# Juggling_Egg_V01.net
KiCad netlist of a schematic drawn in EAGLE
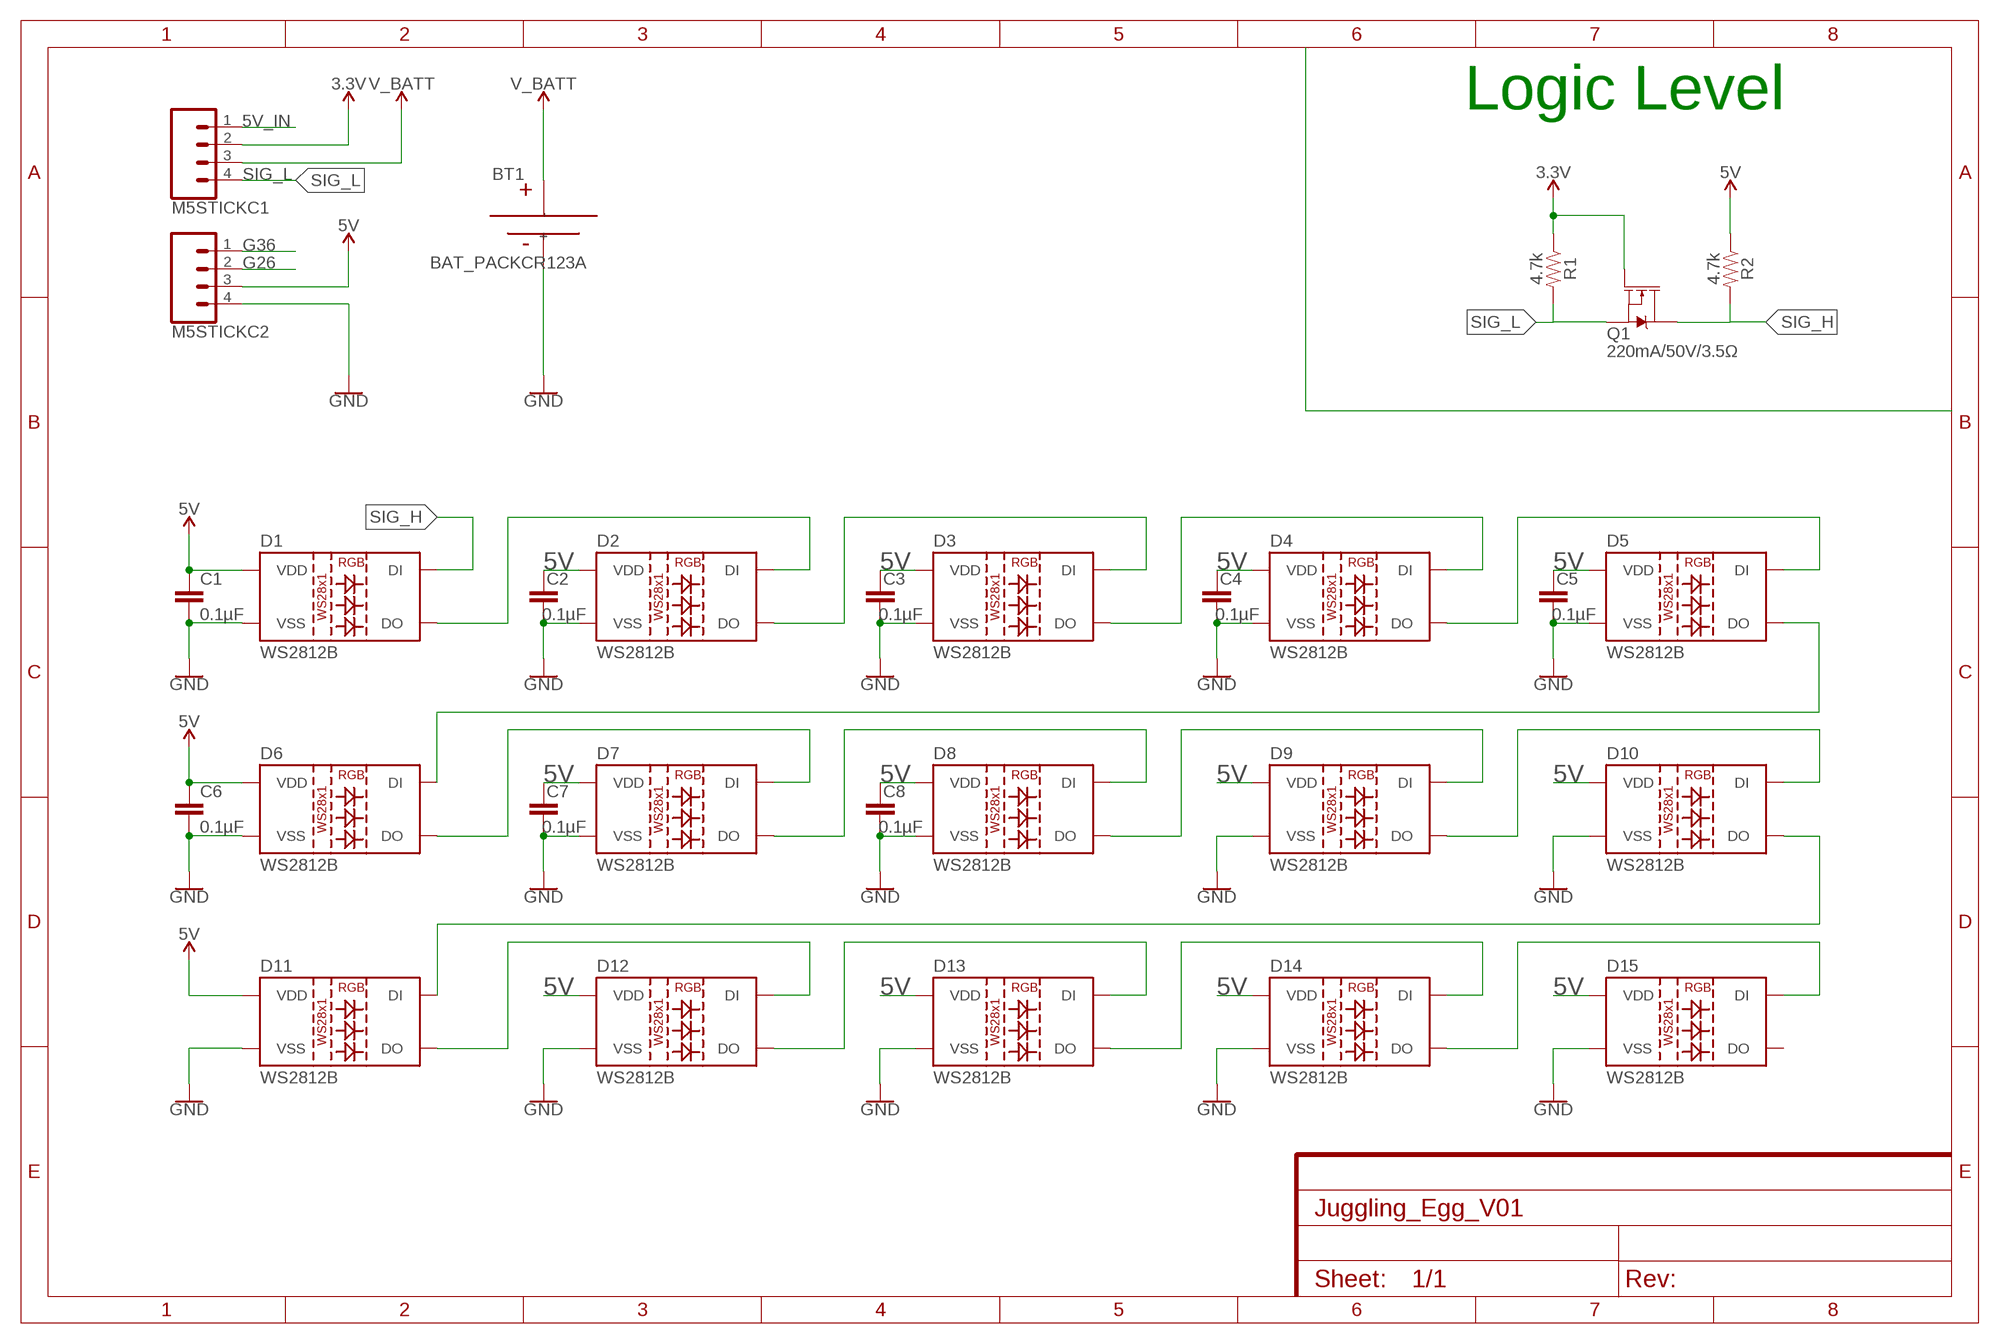
[diagram p0: schematic, sheet 1]

(export (version "E")
  (design (tool "Eeschema 10.0.6"))
  (components
    (comp (ref "BT1")
      (value "BAT_PACKCR123A")
      (footprint "eagle-import:BH123A")
      (fields (field (name "MANUFACTURER") "MPD") (field (name "MPN") "BH123A"))
      (libsource (lib "eagle-import") (part "BAT_PACKCR123A"))
    )
    (comp (ref "C1")
      (value "0.1µF")
      (footprint "eagle-import:0805")
      (libsource (lib "eagle-import") (part "0.33UF/330NF-0805-50V-10%"))
    )
    (comp (ref "C2")
      (value "0.1µF")
      (footprint "eagle-import:0805")
      (libsource (lib "eagle-import") (part "0.33UF/330NF-0805-50V-10%"))
    )
    (comp (ref "C3")
      (value "0.1µF")
      (footprint "eagle-import:0805")
      (libsource (lib "eagle-import") (part "0.33UF/330NF-0805-50V-10%"))
    )
    (comp (ref "C4")
      (value "0.1µF")
      (footprint "eagle-import:0805")
      (libsource (lib "eagle-import") (part "0.33UF/330NF-0805-50V-10%"))
    )
    (comp (ref "C5")
      (value "0.1µF")
      (footprint "eagle-import:0805")
      (libsource (lib "eagle-import") (part "0.33UF/330NF-0805-50V-10%"))
    )
    (comp (ref "C6")
      (value "0.1µF")
      (footprint "eagle-import:0805")
      (libsource (lib "eagle-import") (part "0.33UF/330NF-0805-50V-10%"))
    )
    (comp (ref "C7")
      (value "0.1µF")
      (footprint "eagle-import:0805")
      (libsource (lib "eagle-import") (part "0.33UF/330NF-0805-50V-10%"))
    )
    (comp (ref "C8")
      (value "0.1µF")
      (footprint "eagle-import:0805")
      (libsource (lib "eagle-import") (part "0.33UF/330NF-0805-50V-10%"))
    )
    (comp (ref "D1")
      (value "WS2812B")
      (footprint "eagle-import:WS2812B")
      (libsource (lib "eagle-import") (part "WS2812B"))
    )
    (comp (ref "D2")
      (value "WS2812B")
      (footprint "eagle-import:WS2812B")
      (libsource (lib "eagle-import") (part "WS2812B"))
    )
    (comp (ref "D3")
      (value "WS2812B")
      (footprint "eagle-import:WS2812B")
      (libsource (lib "eagle-import") (part "WS2812B"))
    )
    (comp (ref "D4")
      (value "WS2812B")
      (footprint "eagle-import:WS2812B")
      (libsource (lib "eagle-import") (part "WS2812B"))
    )
    (comp (ref "D5")
      (value "WS2812B")
      (footprint "eagle-import:WS2812B")
      (libsource (lib "eagle-import") (part "WS2812B"))
    )
    (comp (ref "D6")
      (value "WS2812B")
      (footprint "eagle-import:WS2812B")
      (libsource (lib "eagle-import") (part "WS2812B"))
    )
    (comp (ref "D7")
      (value "WS2812B")
      (footprint "eagle-import:WS2812B")
      (libsource (lib "eagle-import") (part "WS2812B"))
    )
    (comp (ref "D8")
      (value "WS2812B")
      (footprint "eagle-import:WS2812B")
      (libsource (lib "eagle-import") (part "WS2812B"))
    )
    (comp (ref "D9")
      (value "WS2812B")
      (footprint "eagle-import:WS2812B")
      (libsource (lib "eagle-import") (part "WS2812B"))
    )
    (comp (ref "D10")
      (value "WS2812B")
      (footprint "eagle-import:WS2812B")
      (libsource (lib "eagle-import") (part "WS2812B"))
    )
    (comp (ref "D11")
      (value "WS2812B")
      (footprint "eagle-import:WS2812B")
      (libsource (lib "eagle-import") (part "WS2812B"))
    )
    (comp (ref "D12")
      (value "WS2812B")
      (footprint "eagle-import:WS2812B")
      (libsource (lib "eagle-import") (part "WS2812B"))
    )
    (comp (ref "D13")
      (value "WS2812B")
      (footprint "eagle-import:WS2812B")
      (libsource (lib "eagle-import") (part "WS2812B"))
    )
    (comp (ref "D14")
      (value "WS2812B")
      (footprint "eagle-import:WS2812B")
      (libsource (lib "eagle-import") (part "WS2812B"))
    )
    (comp (ref "D15")
      (value "WS2812B")
      (footprint "eagle-import:WS2812B")
      (libsource (lib "eagle-import") (part "WS2812B"))
    )
    (comp (ref "M5STICKC1")
      (value "CONN_04SMD")
      (footprint "eagle-import:1X04_SMD_RA_MALE")
      (libsource (lib "eagle-import") (part "CONN_04SMD"))
    )
    (comp (ref "M5STICKC2")
      (value "CONN_04SMD")
      (footprint "eagle-import:1X04_SMD_RA_MALE")
      (libsource (lib "eagle-import") (part "CONN_04SMD"))
    )
    (comp (ref "Q1")
      (value "220mA/50V/3.5Ω")
      (footprint "eagle-import:SOT23-3")
      (libsource (lib "eagle-import") (part "MOSFET-NCH-BSS138"))
    )
    (comp (ref "R1")
      (value "4.7k")
      (footprint "eagle-import:0805")
      (libsource (lib "eagle-import") (part "RESISTOR0805"))
    )
    (comp (ref "R2")
      (value "4.7k")
      (footprint "eagle-import:0805")
      (libsource (lib "eagle-import") (part "RESISTOR0805"))
    )
  )
  (nets
    (net (code "1") (name "/5V_IN") (class "Default")
      (node (ref "M5STICKC1") (pin "1") (pinfunction "1_1") (pintype "passive"))
    )
    (net (code "2") (name "/G26") (class "Default")
      (node (ref "M5STICKC2") (pin "2") (pinfunction "2_2") (pintype "passive"))
    )
    (net (code "3") (name "/G36") (class "Default")
      (node (ref "M5STICKC2") (pin "1") (pinfunction "1_1") (pintype "passive"))
    )
    (net (code "4") (name "3.3V") (class "Default")
      (node (ref "M5STICKC1") (pin "2") (pinfunction "2_2") (pintype "passive"))
      (node (ref "Q1") (pin "1") (pinfunction "G_1") (pintype "bidirectional"))
      (node (ref "R1") (pin "1") (pinfunction "1_1") (pintype "passive"))
    )
    (net (code "5") (name "5V") (class "Default")
      (node (ref "C1") (pin "1") (pinfunction "1_1") (pintype "passive"))
      (node (ref "C2") (pin "2") (pinfunction "2_2") (pintype "passive"))
      (node (ref "C3") (pin "2") (pinfunction "2_2") (pintype "passive"))
      (node (ref "C4") (pin "2") (pinfunction "2_2") (pintype "passive"))
      (node (ref "C5") (pin "2") (pinfunction "2_2") (pintype "passive"))
      (node (ref "C6") (pin "1") (pinfunction "1_1") (pintype "passive"))
      (node (ref "C7") (pin "2") (pinfunction "2_2") (pintype "passive"))
      (node (ref "C8") (pin "2") (pinfunction "2_2") (pintype "passive"))
      (node (ref "D1") (pin "1") (pinfunction "VDD_1") (pintype "bidirectional"))
      (node (ref "D10") (pin "1") (pinfunction "VDD_1") (pintype "bidirectional"))
      (node (ref "D11") (pin "1") (pinfunction "VDD_1") (pintype "bidirectional"))
      (node (ref "D12") (pin "1") (pinfunction "VDD_1") (pintype "bidirectional"))
      (node (ref "D13") (pin "1") (pinfunction "VDD_1") (pintype "bidirectional"))
      (node (ref "D14") (pin "1") (pinfunction "VDD_1") (pintype "bidirectional"))
      (node (ref "D15") (pin "1") (pinfunction "VDD_1") (pintype "bidirectional"))
      (node (ref "D2") (pin "1") (pinfunction "VDD_1") (pintype "bidirectional"))
      (node (ref "D3") (pin "1") (pinfunction "VDD_1") (pintype "bidirectional"))
      (node (ref "D4") (pin "1") (pinfunction "VDD_1") (pintype "bidirectional"))
      (node (ref "D5") (pin "1") (pinfunction "VDD_1") (pintype "bidirectional"))
      (node (ref "D6") (pin "1") (pinfunction "VDD_1") (pintype "bidirectional"))
      (node (ref "D7") (pin "1") (pinfunction "VDD_1") (pintype "bidirectional"))
      (node (ref "D8") (pin "1") (pinfunction "VDD_1") (pintype "bidirectional"))
      (node (ref "D9") (pin "1") (pinfunction "VDD_1") (pintype "bidirectional"))
      (node (ref "M5STICKC2") (pin "3") (pinfunction "3_3") (pintype "passive"))
      (node (ref "R2") (pin "1") (pinfunction "1_1") (pintype "passive"))
    )
    (net (code "6") (name "GND") (class "Default")
      (node (ref "BT1") (pin "-") (pinfunction "-_-") (pintype "bidirectional"))
      (node (ref "C1") (pin "2") (pinfunction "2_2") (pintype "passive"))
      (node (ref "C2") (pin "1") (pinfunction "1_1") (pintype "passive"))
      (node (ref "C3") (pin "1") (pinfunction "1_1") (pintype "passive"))
      (node (ref "C4") (pin "1") (pinfunction "1_1") (pintype "passive"))
      (node (ref "C5") (pin "1") (pinfunction "1_1") (pintype "passive"))
      (node (ref "C6") (pin "2") (pinfunction "2_2") (pintype "passive"))
      (node (ref "C7") (pin "1") (pinfunction "1_1") (pintype "passive"))
      (node (ref "C8") (pin "1") (pinfunction "1_1") (pintype "passive"))
      (node (ref "D1") (pin "3") (pinfunction "VSS_3") (pintype "bidirectional"))
      (node (ref "D10") (pin "3") (pinfunction "VSS_3") (pintype "bidirectional"))
      (node (ref "D11") (pin "3") (pinfunction "VSS_3") (pintype "bidirectional"))
      (node (ref "D12") (pin "3") (pinfunction "VSS_3") (pintype "bidirectional"))
      (node (ref "D13") (pin "3") (pinfunction "VSS_3") (pintype "bidirectional"))
      (node (ref "D14") (pin "3") (pinfunction "VSS_3") (pintype "bidirectional"))
      (node (ref "D15") (pin "3") (pinfunction "VSS_3") (pintype "bidirectional"))
      (node (ref "D2") (pin "3") (pinfunction "VSS_3") (pintype "bidirectional"))
      (node (ref "D3") (pin "3") (pinfunction "VSS_3") (pintype "bidirectional"))
      (node (ref "D4") (pin "3") (pinfunction "VSS_3") (pintype "bidirectional"))
      (node (ref "D5") (pin "3") (pinfunction "VSS_3") (pintype "bidirectional"))
      (node (ref "D6") (pin "3") (pinfunction "VSS_3") (pintype "bidirectional"))
      (node (ref "D7") (pin "3") (pinfunction "VSS_3") (pintype "bidirectional"))
      (node (ref "D8") (pin "3") (pinfunction "VSS_3") (pintype "bidirectional"))
      (node (ref "D9") (pin "3") (pinfunction "VSS_3") (pintype "bidirectional"))
      (node (ref "M5STICKC2") (pin "4") (pinfunction "4_4") (pintype "passive"))
    )
    (net (code "7") (name "Net-(D1-DO)") (class "Default")
      (node (ref "D1") (pin "2") (pinfunction "DO_2") (pintype "bidirectional"))
      (node (ref "D2") (pin "4") (pinfunction "DI_4") (pintype "bidirectional"))
    )
    (net (code "8") (name "Net-(D2-DO)") (class "Default")
      (node (ref "D2") (pin "2") (pinfunction "DO_2") (pintype "bidirectional"))
      (node (ref "D3") (pin "4") (pinfunction "DI_4") (pintype "bidirectional"))
    )
    (net (code "9") (name "Net-(D3-DO)") (class "Default")
      (node (ref "D3") (pin "2") (pinfunction "DO_2") (pintype "bidirectional"))
      (node (ref "D4") (pin "4") (pinfunction "DI_4") (pintype "bidirectional"))
    )
    (net (code "10") (name "Net-(D4-DO)") (class "Default")
      (node (ref "D4") (pin "2") (pinfunction "DO_2") (pintype "bidirectional"))
      (node (ref "D5") (pin "4") (pinfunction "DI_4") (pintype "bidirectional"))
    )
    (net (code "11") (name "Net-(D5-DO)") (class "Default")
      (node (ref "D5") (pin "2") (pinfunction "DO_2") (pintype "bidirectional"))
      (node (ref "D6") (pin "4") (pinfunction "DI_4") (pintype "bidirectional"))
    )
    (net (code "12") (name "Net-(D6-DO)") (class "Default")
      (node (ref "D6") (pin "2") (pinfunction "DO_2") (pintype "bidirectional"))
      (node (ref "D7") (pin "4") (pinfunction "DI_4") (pintype "bidirectional"))
    )
    (net (code "13") (name "Net-(D7-DO)") (class "Default")
      (node (ref "D7") (pin "2") (pinfunction "DO_2") (pintype "bidirectional"))
      (node (ref "D8") (pin "4") (pinfunction "DI_4") (pintype "bidirectional"))
    )
    (net (code "14") (name "Net-(D8-DO)") (class "Default")
      (node (ref "D8") (pin "2") (pinfunction "DO_2") (pintype "bidirectional"))
      (node (ref "D9") (pin "4") (pinfunction "DI_4") (pintype "bidirectional"))
    )
    (net (code "15") (name "Net-(D10-DI)") (class "Default")
      (node (ref "D10") (pin "4") (pinfunction "DI_4") (pintype "bidirectional"))
      (node (ref "D9") (pin "2") (pinfunction "DO_2") (pintype "bidirectional"))
    )
    (net (code "16") (name "Net-(D10-DO)") (class "Default")
      (node (ref "D10") (pin "2") (pinfunction "DO_2") (pintype "bidirectional"))
      (node (ref "D11") (pin "4") (pinfunction "DI_4") (pintype "bidirectional"))
    )
    (net (code "17") (name "Net-(D11-DO)") (class "Default")
      (node (ref "D11") (pin "2") (pinfunction "DO_2") (pintype "bidirectional"))
      (node (ref "D12") (pin "4") (pinfunction "DI_4") (pintype "bidirectional"))
    )
    (net (code "18") (name "Net-(D12-DO)") (class "Default")
      (node (ref "D12") (pin "2") (pinfunction "DO_2") (pintype "bidirectional"))
      (node (ref "D13") (pin "4") (pinfunction "DI_4") (pintype "bidirectional"))
    )
    (net (code "19") (name "Net-(D13-DO)") (class "Default")
      (node (ref "D13") (pin "2") (pinfunction "DO_2") (pintype "bidirectional"))
      (node (ref "D14") (pin "4") (pinfunction "DI_4") (pintype "bidirectional"))
    )
    (net (code "20") (name "Net-(D14-DO)") (class "Default")
      (node (ref "D14") (pin "2") (pinfunction "DO_2") (pintype "bidirectional"))
      (node (ref "D15") (pin "4") (pinfunction "DI_4") (pintype "bidirectional"))
    )
    (net (code "21") (name "SIG_H") (class "Default")
      (node (ref "D1") (pin "4") (pinfunction "DI_4") (pintype "bidirectional"))
      (node (ref "Q1") (pin "3") (pinfunction "D_3") (pintype "bidirectional"))
      (node (ref "R2") (pin "2") (pinfunction "2_2") (pintype "passive"))
    )
    (net (code "22") (name "SIG_L") (class "Default")
      (node (ref "M5STICKC1") (pin "4") (pinfunction "4_4") (pintype "passive"))
      (node (ref "Q1") (pin "2") (pinfunction "S_2") (pintype "bidirectional"))
      (node (ref "R1") (pin "2") (pinfunction "2_2") (pintype "passive"))
    )
    (net (code "23") (name "V_BATT") (class "Default")
      (node (ref "BT1") (pin "+") (pinfunction "+_+") (pintype "bidirectional"))
      (node (ref "M5STICKC1") (pin "3") (pinfunction "3_3") (pintype "passive"))
    )
    (net (code "24") (name "unconnected-(D15-DO-Pad2)") (class "Default")
      (node (ref "D15") (pin "2") (pinfunction "DO_2") (pintype "bidirectional"))
    )
  )
)
